# lat_encamp_v2.net
KiCad netlist of a schematic drawn in EAGLE
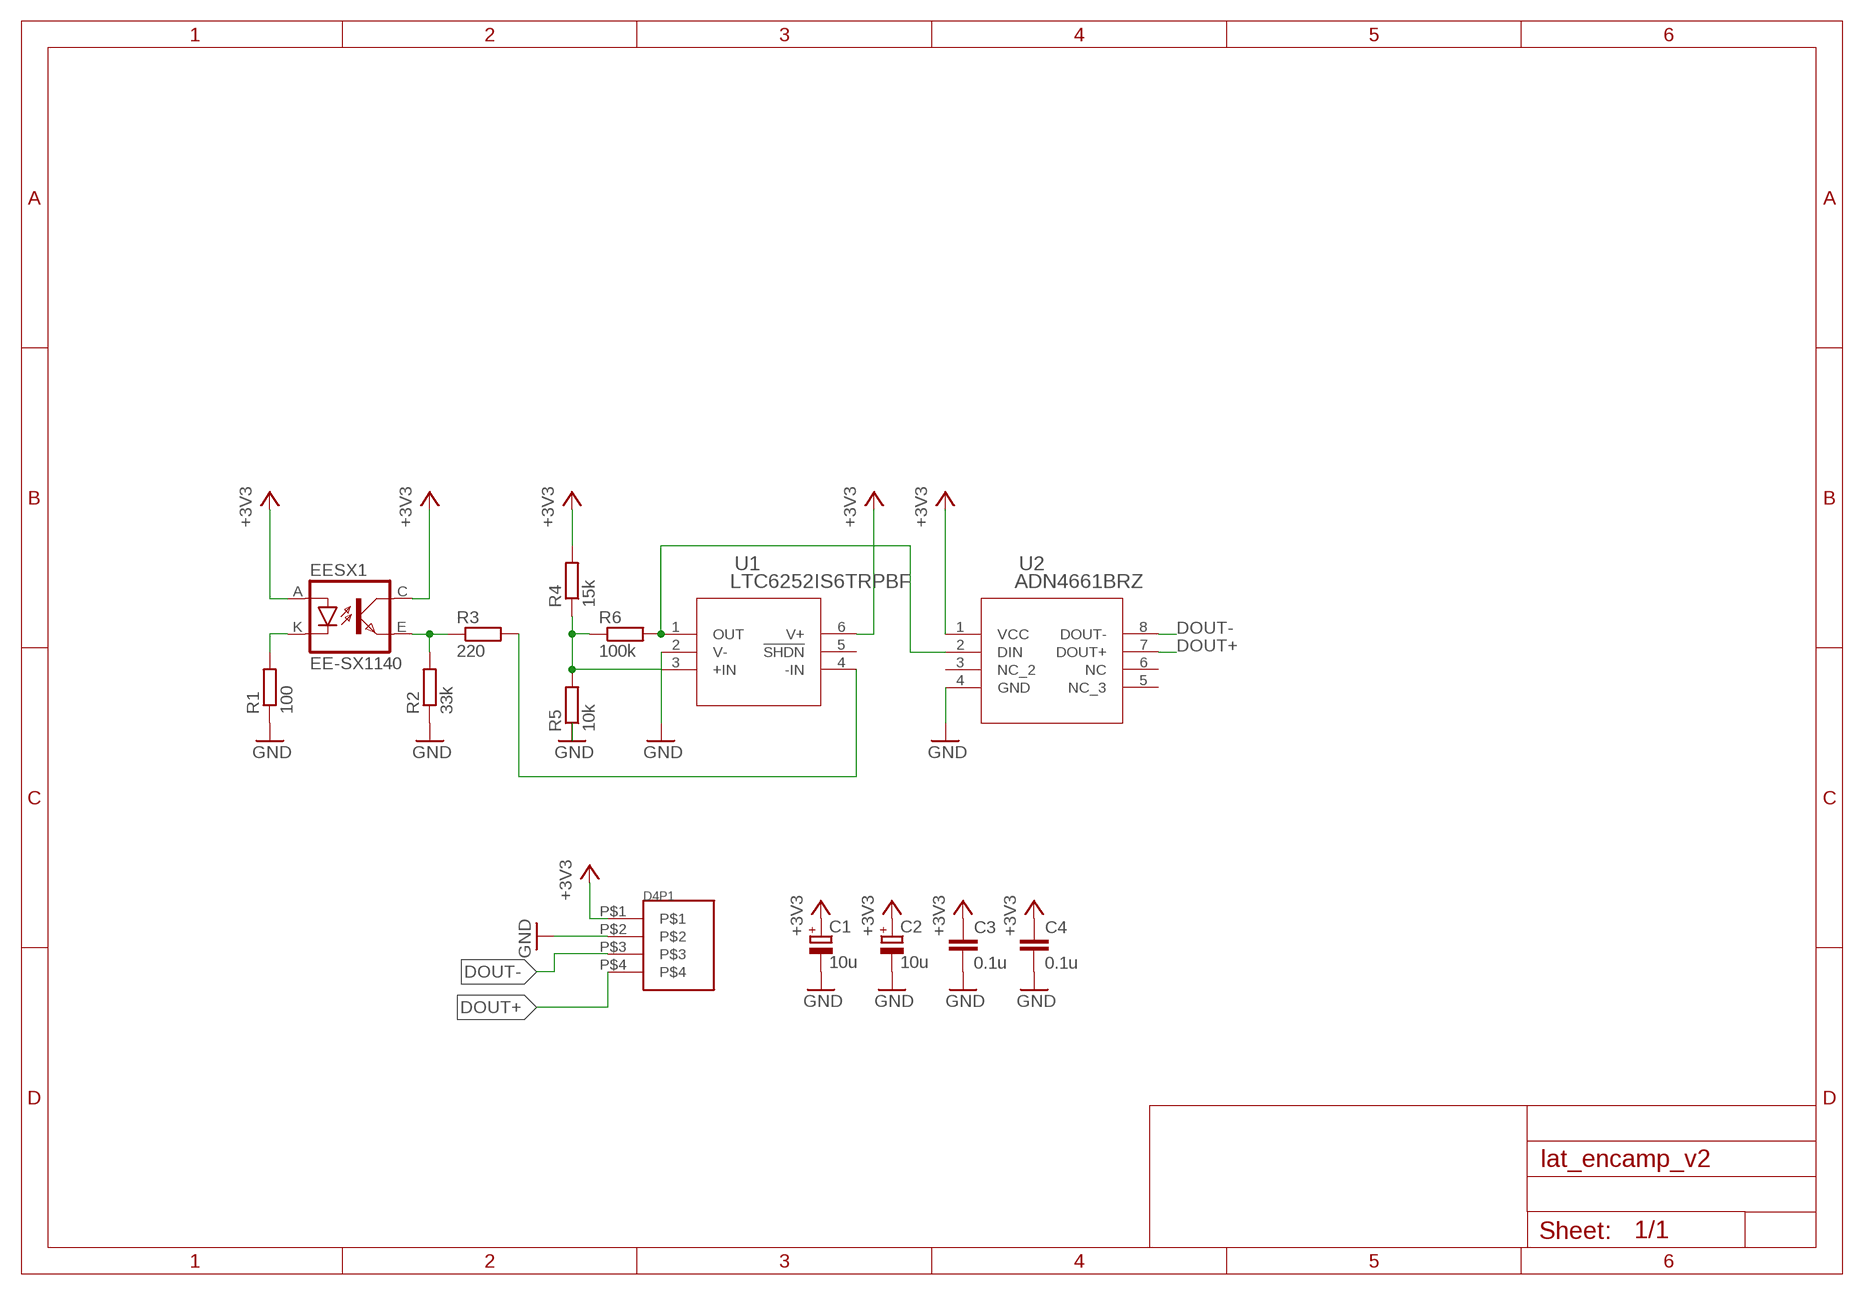
[diagram p0: schematic, sheet 1]

(export (version "E")
  (design (tool "Eeschema 10.0.6"))
  (components
    (comp (ref "C1")
      (value "10u")
      (footprint "eagle-import:SMC_A")
      (libsource (lib "eagle-import") (part "CPOL-EUSMCA"))
    )
    (comp (ref "C2")
      (value "10u")
      (footprint "eagle-import:SMC_A")
      (libsource (lib "eagle-import") (part "CPOL-EUSMCA"))
    )
    (comp (ref "C3")
      (value "0.1u")
      (footprint "eagle-import:C0603")
      (libsource (lib "eagle-import") (part "C-EUC0603"))
    )
    (comp (ref "C4")
      (value "0.1u")
      (footprint "eagle-import:C0603")
      (libsource (lib "eagle-import") (part "C-EUC0603"))
    )
    (comp (ref "D4P1")
      (value "DF1E-4P")
      (footprint "eagle-import:DF1E-4P")
      (libsource (lib "eagle-import") (part "DF1E-4P"))
    )
    (comp (ref "EESX1")
      (value "EE-SX1140")
      (footprint "eagle-import:EE-SX1140")
      (libsource (lib "eagle-import") (part "EE-SX1140"))
    )
    (comp (ref "R1")
      (value "100")
      (footprint "eagle-import:R0603")
      (libsource (lib "eagle-import") (part "R-EU_R0603"))
    )
    (comp (ref "R2")
      (value "33k")
      (footprint "eagle-import:R0603")
      (libsource (lib "eagle-import") (part "R-EU_R0603"))
    )
    (comp (ref "R3")
      (value "220")
      (footprint "eagle-import:R0603")
      (libsource (lib "eagle-import") (part "R-EU_R0603"))
    )
    (comp (ref "R4")
      (value "15k")
      (footprint "eagle-import:R0603")
      (libsource (lib "eagle-import") (part "R-EU_R0603"))
    )
    (comp (ref "R5")
      (value "10k")
      (footprint "eagle-import:R0603")
      (libsource (lib "eagle-import") (part "R-EU_R0603"))
    )
    (comp (ref "R6")
      (value "100k")
      (footprint "eagle-import:R0603")
      (libsource (lib "eagle-import") (part "R-EU_R0603"))
    )
    (comp (ref "U1")
      (value "LTC6252IS6TRPBF")
      (footprint "eagle-import:TSOT-23_S6_LIT")
      (fields (field (name "MANUFACTURER_PART_NUMBER") "LTC6252IS6#TRPBF"))
      (libsource (lib "eagle-import") (part "LTC6252IS6TRPBF"))
    )
    (comp (ref "U2")
      (value "ADN4661BRZ")
      (footprint "eagle-import:R_8_ADI")
      (libsource (lib "eagle-import") (part "ADN4661BRZ"))
    )
  )
  (nets
    (net (code "1") (name "+3V3") (class "Default")
      (node (ref "C1") (pin "+") (pinfunction "+_+") (pintype "passive"))
      (node (ref "C2") (pin "+") (pinfunction "+_+") (pintype "passive"))
      (node (ref "C3") (pin "1") (pinfunction "1_1") (pintype "passive"))
      (node (ref "C4") (pin "1") (pinfunction "1_1") (pintype "passive"))
      (node (ref "D4P1") (pin "P$1") (pinfunction "P$1_P$1") (pintype "bidirectional"))
      (node (ref "EESX1") (pin "A") (pinfunction "A_A") (pintype "passive"))
      (node (ref "EESX1") (pin "C") (pinfunction "COL_C") (pintype "passive"))
      (node (ref "R4") (pin "2") (pinfunction "2_2") (pintype "passive"))
      (node (ref "U1") (pin "6") (pinfunction "V+_6") (pintype "power_in"))
      (node (ref "U2") (pin "1") (pinfunction "VCC_1") (pintype "power_in"))
    )
    (net (code "2") (name "DOUT+") (class "Default")
      (node (ref "D4P1") (pin "P$4") (pinfunction "P$4_P$4") (pintype "bidirectional"))
      (node (ref "U2") (pin "7") (pinfunction "DOUT+_7") (pintype "passive"))
    )
    (net (code "3") (name "DOUT-") (class "Default")
      (node (ref "D4P1") (pin "P$3") (pinfunction "P$3_P$3") (pintype "bidirectional"))
      (node (ref "U2") (pin "8") (pinfunction "DOUT-_8") (pintype "passive"))
    )
    (net (code "4") (name "GND") (class "Default")
      (node (ref "C1") (pin "-") (pinfunction "-_-") (pintype "passive"))
      (node (ref "C2") (pin "-") (pinfunction "-_-") (pintype "passive"))
      (node (ref "C3") (pin "2") (pinfunction "2_2") (pintype "passive"))
      (node (ref "C4") (pin "2") (pinfunction "2_2") (pintype "passive"))
      (node (ref "D4P1") (pin "P$2") (pinfunction "P$2_P$2") (pintype "bidirectional"))
      (node (ref "R1") (pin "1") (pinfunction "1_1") (pintype "passive"))
      (node (ref "R2") (pin "1") (pinfunction "1_1") (pintype "passive"))
      (node (ref "R5") (pin "1") (pinfunction "1_1") (pintype "passive"))
      (node (ref "U1") (pin "2") (pinfunction "V-_2") (pintype "power_in"))
      (node (ref "U2") (pin "4") (pinfunction "GND_4") (pintype "passive"))
    )
    (net (code "5") (name "Net-(EESX1-C)") (class "Default")
      (node (ref "EESX1") (pin "K") (pinfunction "C_K") (pintype "passive"))
      (node (ref "R1") (pin "2") (pinfunction "2_2") (pintype "passive"))
    )
    (net (code "6") (name "Net-(EESX1-EMIT)") (class "Default")
      (node (ref "EESX1") (pin "E") (pinfunction "EMIT_E") (pintype "passive"))
      (node (ref "R2") (pin "2") (pinfunction "2_2") (pintype "passive"))
      (node (ref "R3") (pin "1") (pinfunction "1_1") (pintype "passive"))
    )
    (net (code "7") (name "Net-(U1-+IN)") (class "Default")
      (node (ref "R4") (pin "1") (pinfunction "1_1") (pintype "passive"))
      (node (ref "R5") (pin "2") (pinfunction "2_2") (pintype "passive"))
      (node (ref "R6") (pin "1") (pinfunction "1_1") (pintype "passive"))
      (node (ref "U1") (pin "3") (pinfunction "+IN_3") (pintype "input"))
    )
    (net (code "8") (name "Net-(U1--IN)") (class "Default")
      (node (ref "R3") (pin "2") (pinfunction "2_2") (pintype "passive"))
      (node (ref "U1") (pin "4") (pinfunction "-IN_4") (pintype "input"))
    )
    (net (code "9") (name "Net-(U1-OUT)") (class "Default")
      (node (ref "R6") (pin "2") (pinfunction "2_2") (pintype "passive"))
      (node (ref "U1") (pin "1") (pinfunction "OUT_1") (pintype "output"))
      (node (ref "U2") (pin "2") (pinfunction "DIN_2") (pintype "passive"))
    )
    (net (code "10") (name "unconnected-(U1-~{SHDN}-Pad5)") (class "Default")
      (node (ref "U1") (pin "5") (pinfunction "~{SHDN}_5") (pintype "passive"))
    )
    (net (code "11") (name "unconnected-(U2-NC-Pad6)") (class "Default")
      (node (ref "U2") (pin "6") (pinfunction "NC_6") (pintype "passive"))
    )
    (net (code "12") (name "unconnected-(U2-NC_2-Pad3)") (class "Default")
      (node (ref "U2") (pin "3") (pinfunction "NC_2_3") (pintype "passive"))
    )
    (net (code "13") (name "unconnected-(U2-NC_3-Pad5)") (class "Default")
      (node (ref "U2") (pin "5") (pinfunction "NC_3_5") (pintype "passive"))
    )
  )
)
